# Sorting_servo.net
KiCad netlist of a schematic drawn in Altium Designer
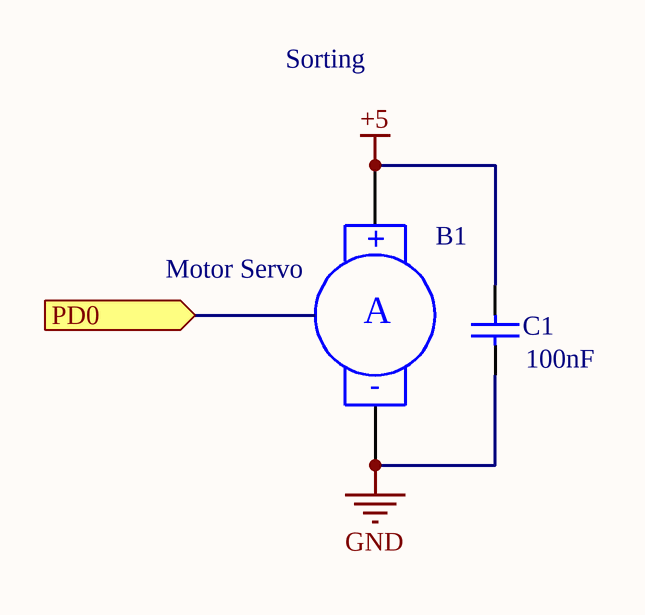
[diagram p0: Sorting_servo.SchDoc]

(export (version "E")
  (design (tool "Eeschema 10.0.6"))
  (components
    (comp (ref "B1")
      (value "Motor Servo")
      (footprint "RAD-0.4")
      (description "Servo Motor")
      (fields (field (name "PUBLISHER") "Altium Limited"))
      (libsource (lib "Miscellaneous Devices") (part "Motor Servo"))
    )
    (comp (ref "C1")
      (value "100nF")
      (footprint "RAD-0.3")
      (description "Capacitor")
      (fields (field (name "Comment") "Cap") (field (name "PUBLISHER") "Altium Limited"))
      (libsource (lib "Miscellaneous Devices") (part "Cap"))
    )
  )
  (nets
    (net (code "1") (name "+5") (class "Default")
      (node (ref "B1") (pin "1") (pinfunction "+_1") (pintype "passive"))
      (node (ref "C1") (pin "2") (pinfunction "2_2") (pintype "passive"))
    )
    (net (code "3") (name "GND") (class "Default")
      (node (ref "B1") (pin "2") (pinfunction "-_2") (pintype "passive"))
      (node (ref "C1") (pin "1") (pinfunction "1_1") (pintype "passive"))
    )
  )
)
